# CAP_MATRIX_IN.net
KiCad netlist of a schematic drawn in Altium Designer
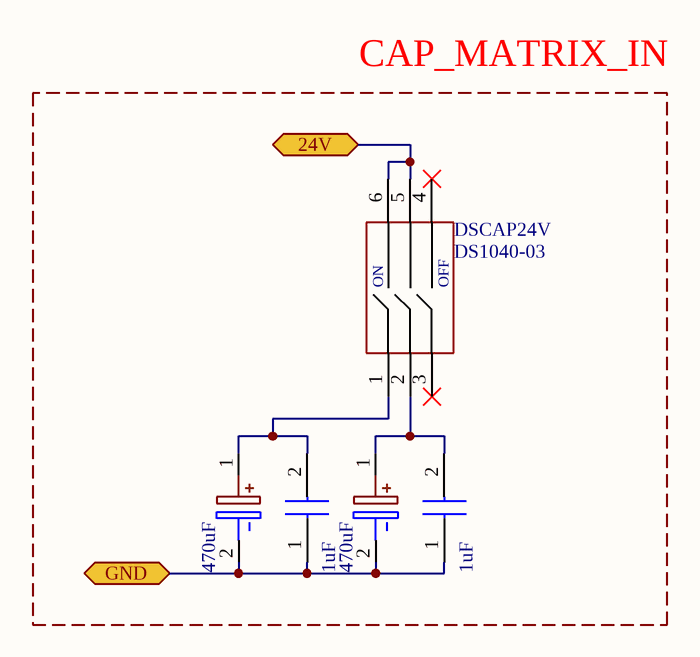
[diagram p0: CAP_MATRIX_IN.SchDoc]

(export (version "E")
  (design (tool "Eeschema 10.0.6"))
  (components
    (comp (ref "CAPCE1")
      (value "1uF")
      (footprint "К10-17Б")
      (description "К10-17Б")
      (libsource (lib "Components_Robots") (part "CAP"))
    )
    (comp (ref "CAPCE2")
      (value "1uF")
      (footprint "К10-17Б")
      (description "К10-17Б")
      (libsource (lib "Components_Robots") (part "CAP"))
    )
    (comp (ref "CAPEL1")
      (value "470uF")
      (footprint "CAP-12.5x13.5")
      (description "YUQINGXIN")
      (libsource (lib "Components_Robots") (part "CAP-12.5x13.5"))
    )
    (comp (ref "CAPEL2")
      (value "470uF")
      (footprint "CAP-12.5x13.5")
      (description "YUQINGXIN")
      (libsource (lib "Components_Robots") (part "CAP-12.5x13.5"))
    )
    (comp (ref "DSCAP24V")
      (value "DS1040-03")
      (footprint "DS1040-03")
      (description "DS1040-03RN")
      (libsource (lib "Components_Robots") (part "DS1040-03"))
    )
  )
  (nets
    (net (code "1") (name "/24V") (class "Default")
      (node (ref "DSCAP24V") (pin "5") (pinfunction "NO_3_5") (pintype "passive"))
      (node (ref "DSCAP24V") (pin "6") (pinfunction "NO_4_6") (pintype "passive"))
    )
    (net (code "2") (name "/GND") (class "Default")
      (node (ref "CAPCE1") (pin "1") (pinfunction "1_1") (pintype "passive"))
      (node (ref "CAPCE2") (pin "1") (pinfunction "1_1") (pintype "passive"))
      (node (ref "CAPEL1") (pin "2") (pinfunction "-_2") (pintype "passive"))
      (node (ref "CAPEL2") (pin "2") (pinfunction "-_2") (pintype "passive"))
    )
    (net (code "3") (name "Net-(CAPEL1-+)") (class "Default")
      (node (ref "CAPCE1") (pin "2") (pinfunction "2_2") (pintype "passive"))
      (node (ref "CAPEL1") (pin "1") (pinfunction "+_1") (pintype "passive"))
      (node (ref "DSCAP24V") (pin "1") (pinfunction "COM_1_1") (pintype "passive"))
    )
    (net (code "4") (name "Net-(CAPEL2-+)") (class "Default")
      (node (ref "CAPCE2") (pin "2") (pinfunction "2_2") (pintype "passive"))
      (node (ref "CAPEL2") (pin "1") (pinfunction "+_1") (pintype "passive"))
      (node (ref "DSCAP24V") (pin "2") (pinfunction "COM_2_2") (pintype "passive"))
    )
    (net (code "5") (name "unconnected-(DSCAP24V-COM_3-Pad3)") (class "Default")
      (node (ref "DSCAP24V") (pin "3") (pinfunction "COM_3_3") (pintype "passive+no_connect"))
    )
    (net (code "6") (name "unconnected-(DSCAP24V-NO_2-Pad4)") (class "Default")
      (node (ref "DSCAP24V") (pin "4") (pinfunction "NO_2_4") (pintype "passive+no_connect"))
    )
  )
)
